# Particle_Feather_AdapterFeb2019v1.net
KiCad netlist of a schematic drawn in EAGLE
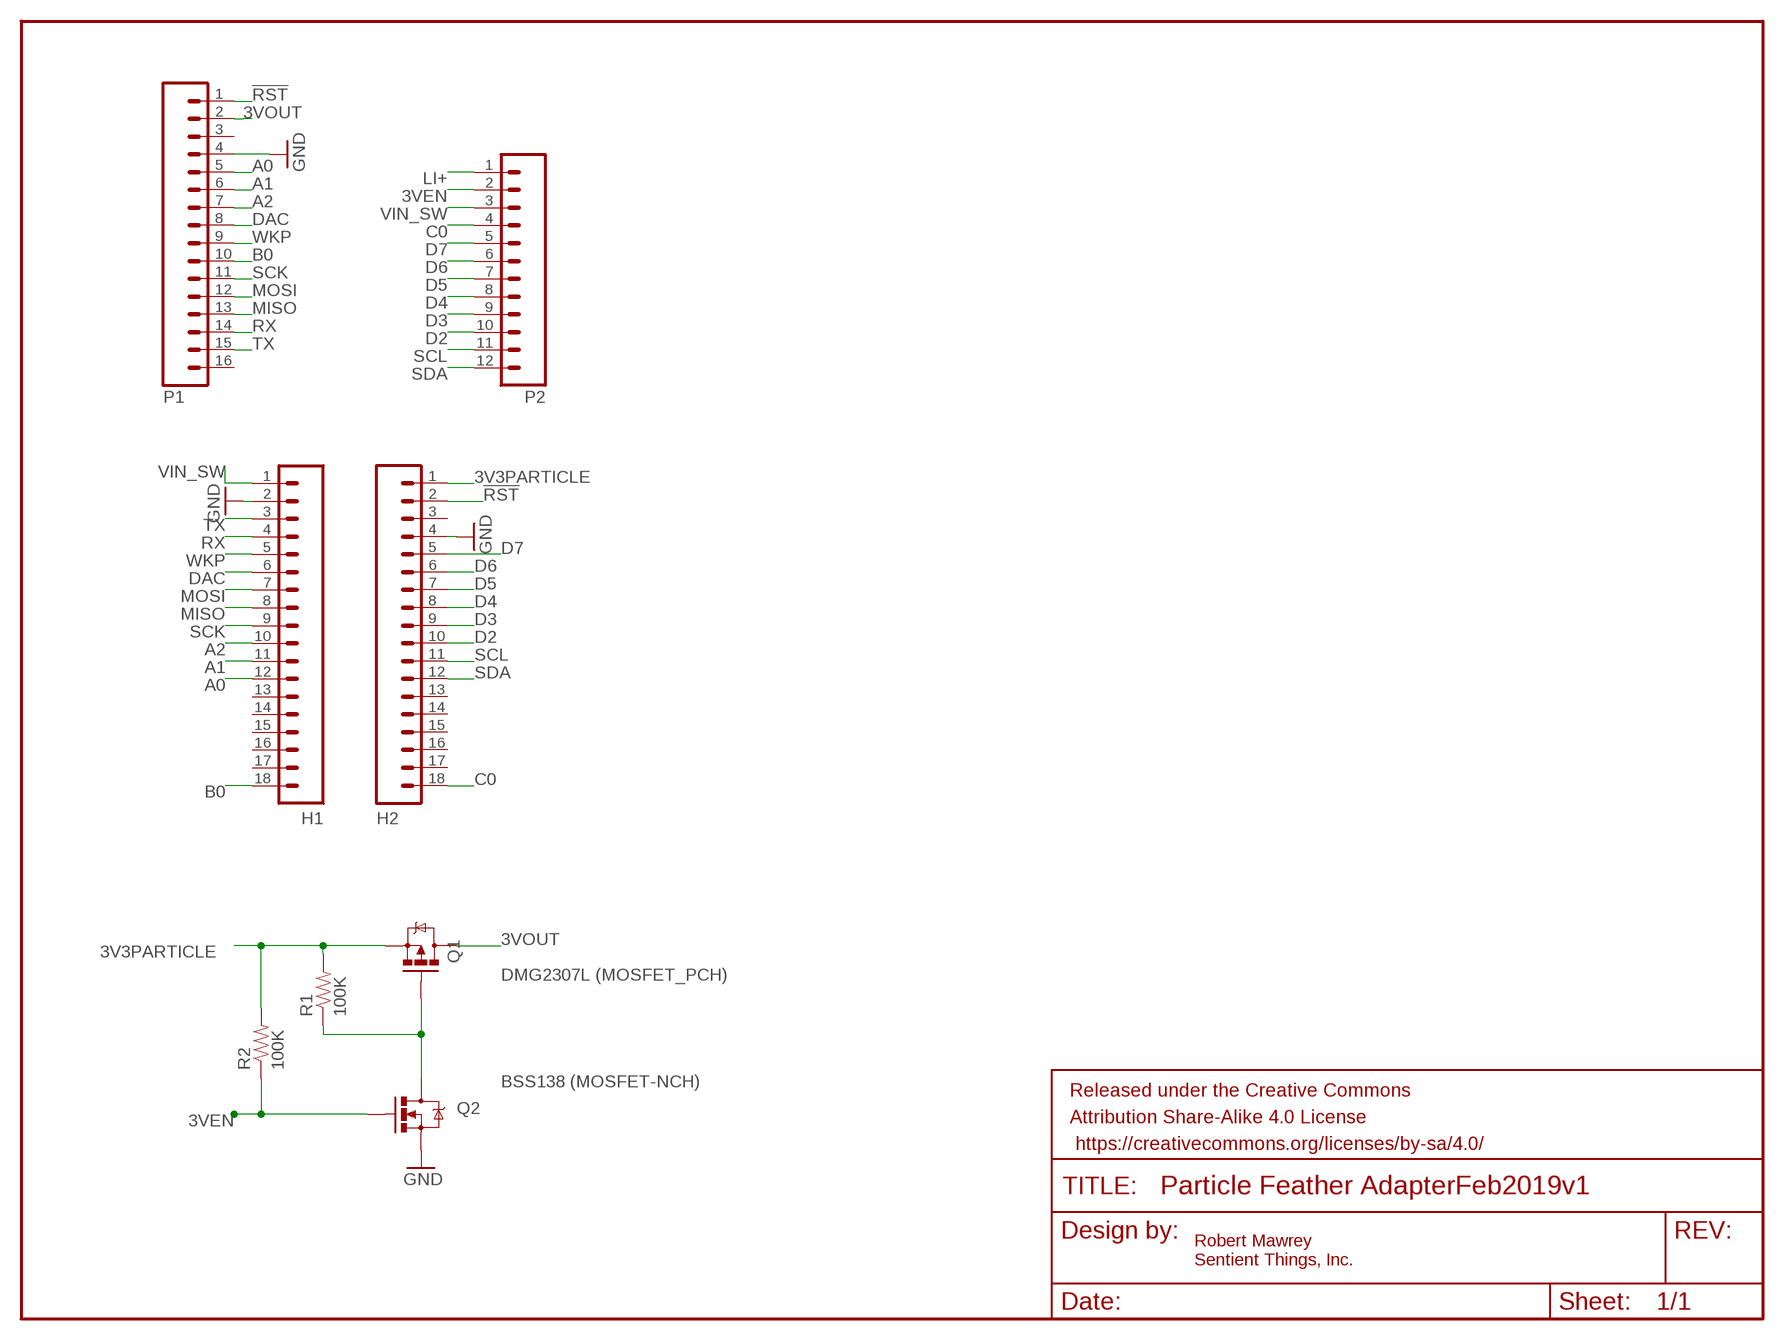
[diagram p0: schematic, sheet 1]

(export (version "E")
  (design (tool "Eeschema 10.0.6"))
  (components
    (comp (ref "FRAME1")
      (value "FRAME-LETTER")
      (footprint "eagle-import:CREATIVE_COMMONS")
      (fields (field (name "PARTNO") "DNP"))
      (libsource (lib "eagle-import") (part "FRAME-LETTER"))
    )
    (comp (ref "FRAME2")
      (value "FRAME-LETTER")
      (footprint "eagle-import:CREATIVE_COMMONS")
      (fields (field (name "PARTNO") "DNP"))
      (libsource (lib "eagle-import") (part "FRAME-LETTER"))
    )
    (comp (ref "H1")
      (value "M18-MILLMAX")
      (footprint "eagle-import:1X18-01SMD")
      (fields (field (name "PARTNO") "310-43-118-41-105000"))
      (libsource (lib "eagle-import") (part "M18-MILLMAX"))
    )
    (comp (ref "H2")
      (value "M18-MILLMAX")
      (footprint "eagle-import:1X18-01SMD")
      (fields (field (name "PARTNO") "310-43-118-41-105000"))
      (libsource (lib "eagle-import") (part "M18-MILLMAX"))
    )
    (comp (ref "P1")
      (value "M16-FEATHER")
      (footprint "eagle-import:1X16-01SMDRIGHT")
      (fields (field (name "PARTNO") "68016-116HLF"))
      (libsource (lib "eagle-import") (part "M16-FEATHER"))
    )
    (comp (ref "P2")
      (value "M12-FEATHER")
      (footprint "eagle-import:1X12-01SMDLEFT")
      (fields (field (name "PARTNO") "68016-212HLF"))
      (libsource (lib "eagle-import") (part "M12-FEATHER"))
    )
    (comp (ref "Q1")
      (value "MOSFET-PCHANNELSMD")
      (footprint "eagle-import:SOT23-3")
      (fields (field (name "PARTNO") "DMG2307L-7"))
      (libsource (lib "eagle-import") (part "MOSFET-PCHANNELSMD"))
    )
    (comp (ref "Q2")
      (value "MOSFET-NCHANNELSMD")
      (footprint "eagle-import:MAWREY_SOT23-3")
      (fields (field (name "PARTNO") "BSS138"))
      (libsource (lib "eagle-import") (part "MOSFET-NCHANNELSMD"))
    )
    (comp (ref "R1")
      (value "100K")
      (footprint "eagle-import:0603-RES")
      (fields (field (name "PARTNO") "RC0603JR-07100KL"))
      (libsource (lib "eagle-import") (part "RESISTOR0603-RES"))
    )
    (comp (ref "R2")
      (value "100K")
      (footprint "eagle-import:0603-RES")
      (fields (field (name "PARTNO") "RC0603JR-07100KL"))
      (libsource (lib "eagle-import") (part "RESISTOR0603-RES"))
    )
  )
  (nets
    (net (code "1") (name "/3V3PARTICLE") (class "Default")
      (node (ref "H2") (pin "1") (pinfunction "1_1") (pintype "passive"))
      (node (ref "Q1") (pin "2") (pinfunction "S_2") (pintype "passive"))
      (node (ref "R1") (pin "2") (pinfunction "2_2") (pintype "passive"))
      (node (ref "R2") (pin "2") (pinfunction "2_2") (pintype "passive"))
    )
    (net (code "2") (name "/3VEN") (class "Default")
      (node (ref "P2") (pin "2") (pinfunction "2_2") (pintype "passive"))
      (node (ref "Q2") (pin "1") (pinfunction "G_1") (pintype "passive"))
      (node (ref "R2") (pin "1") (pinfunction "1_1") (pintype "passive"))
    )
    (net (code "3") (name "/3VOUT") (class "Default")
      (node (ref "P1") (pin "2") (pinfunction "2_2") (pintype "passive"))
      (node (ref "Q1") (pin "3") (pinfunction "D_3") (pintype "passive"))
    )
    (net (code "4") (name "/A0") (class "Default")
      (node (ref "H1") (pin "12") (pinfunction "12_12") (pintype "passive"))
      (node (ref "P1") (pin "5") (pinfunction "5_5") (pintype "passive"))
    )
    (net (code "5") (name "/A1") (class "Default")
      (node (ref "H1") (pin "11") (pinfunction "11_11") (pintype "passive"))
      (node (ref "P1") (pin "6") (pinfunction "6_6") (pintype "passive"))
    )
    (net (code "6") (name "/A2") (class "Default")
      (node (ref "H1") (pin "10") (pinfunction "10_10") (pintype "passive"))
      (node (ref "P1") (pin "7") (pinfunction "7_7") (pintype "passive"))
    )
    (net (code "7") (name "/B0") (class "Default")
      (node (ref "H1") (pin "18") (pinfunction "18_18") (pintype "passive"))
      (node (ref "P1") (pin "10") (pinfunction "10_10") (pintype "passive"))
    )
    (net (code "8") (name "/C0") (class "Default")
      (node (ref "H2") (pin "18") (pinfunction "18_18") (pintype "passive"))
      (node (ref "P2") (pin "4") (pinfunction "4_4") (pintype "passive"))
    )
    (net (code "9") (name "/D2") (class "Default")
      (node (ref "H2") (pin "10") (pinfunction "10_10") (pintype "passive"))
      (node (ref "P2") (pin "10") (pinfunction "10_10") (pintype "passive"))
    )
    (net (code "10") (name "/D3") (class "Default")
      (node (ref "H2") (pin "9") (pinfunction "9_9") (pintype "passive"))
      (node (ref "P2") (pin "9") (pinfunction "9_9") (pintype "passive"))
    )
    (net (code "11") (name "/D4") (class "Default")
      (node (ref "H2") (pin "8") (pinfunction "8_8") (pintype "passive"))
      (node (ref "P2") (pin "8") (pinfunction "8_8") (pintype "passive"))
    )
    (net (code "12") (name "/D5") (class "Default")
      (node (ref "H2") (pin "7") (pinfunction "7_7") (pintype "passive"))
      (node (ref "P2") (pin "7") (pinfunction "7_7") (pintype "passive"))
    )
    (net (code "13") (name "/D6") (class "Default")
      (node (ref "H2") (pin "6") (pinfunction "6_6") (pintype "passive"))
      (node (ref "P2") (pin "6") (pinfunction "6_6") (pintype "passive"))
    )
    (net (code "14") (name "/D7") (class "Default")
      (node (ref "H2") (pin "5") (pinfunction "5_5") (pintype "passive"))
      (node (ref "P2") (pin "5") (pinfunction "5_5") (pintype "passive"))
    )
    (net (code "15") (name "/DAC") (class "Default")
      (node (ref "H1") (pin "6") (pinfunction "6_6") (pintype "passive"))
      (node (ref "P1") (pin "8") (pinfunction "8_8") (pintype "passive"))
    )
    (net (code "16") (name "/LI+") (class "Default")
      (node (ref "P2") (pin "1") (pinfunction "1_1") (pintype "passive"))
    )
    (net (code "17") (name "/MISO") (class "Default")
      (node (ref "H1") (pin "8") (pinfunction "8_8") (pintype "passive"))
      (node (ref "P1") (pin "13") (pinfunction "13_13") (pintype "passive"))
    )
    (net (code "18") (name "/MOSI") (class "Default")
      (node (ref "H1") (pin "7") (pinfunction "7_7") (pintype "passive"))
      (node (ref "P1") (pin "12") (pinfunction "12_12") (pintype "passive"))
    )
    (net (code "19") (name "/RX") (class "Default")
      (node (ref "H1") (pin "4") (pinfunction "4_4") (pintype "passive"))
      (node (ref "P1") (pin "14") (pinfunction "14_14") (pintype "passive"))
    )
    (net (code "20") (name "/SCK") (class "Default")
      (node (ref "H1") (pin "9") (pinfunction "9_9") (pintype "passive"))
      (node (ref "P1") (pin "11") (pinfunction "11_11") (pintype "passive"))
    )
    (net (code "21") (name "/SCL") (class "Default")
      (node (ref "H2") (pin "11") (pinfunction "11_11") (pintype "passive"))
      (node (ref "P2") (pin "11") (pinfunction "11_11") (pintype "passive"))
    )
    (net (code "22") (name "/SDA") (class "Default")
      (node (ref "H2") (pin "12") (pinfunction "12_12") (pintype "passive"))
      (node (ref "P2") (pin "12") (pinfunction "12_12") (pintype "passive"))
    )
    (net (code "23") (name "/TX") (class "Default")
      (node (ref "H1") (pin "3") (pinfunction "3_3") (pintype "passive"))
      (node (ref "P1") (pin "15") (pinfunction "15_15") (pintype "passive"))
    )
    (net (code "24") (name "/VIN_SW") (class "Default")
      (node (ref "H1") (pin "1") (pinfunction "1_1") (pintype "passive"))
      (node (ref "P2") (pin "3") (pinfunction "3_3") (pintype "passive"))
    )
    (net (code "25") (name "/WKP") (class "Default")
      (node (ref "H1") (pin "5") (pinfunction "5_5") (pintype "passive"))
      (node (ref "P1") (pin "9") (pinfunction "9_9") (pintype "passive"))
    )
    (net (code "26") (name "/~{RST}") (class "Default")
      (node (ref "H2") (pin "2") (pinfunction "2_2") (pintype "passive"))
      (node (ref "P1") (pin "1") (pinfunction "1_1") (pintype "passive"))
    )
    (net (code "27") (name "GND") (class "Default")
      (node (ref "H1") (pin "2") (pinfunction "2_2") (pintype "passive"))
      (node (ref "H2") (pin "4") (pinfunction "4_4") (pintype "passive"))
      (node (ref "P1") (pin "4") (pinfunction "4_4") (pintype "passive"))
      (node (ref "Q2") (pin "2") (pinfunction "S_2") (pintype "passive"))
    )
    (net (code "28") (name "Net-(Q1-G)") (class "Default")
      (node (ref "Q1") (pin "1") (pinfunction "G_1") (pintype "passive"))
      (node (ref "Q2") (pin "3") (pinfunction "D_3") (pintype "passive"))
      (node (ref "R1") (pin "1") (pinfunction "1_1") (pintype "passive"))
    )
    (net (code "29") (name "unconnected-(H1-Pad13)") (class "Default")
      (node (ref "H1") (pin "13") (pinfunction "13_13") (pintype "passive"))
    )
    (net (code "30") (name "unconnected-(H1-Pad14)") (class "Default")
      (node (ref "H1") (pin "14") (pinfunction "14_14") (pintype "passive"))
    )
    (net (code "31") (name "unconnected-(H1-Pad15)") (class "Default")
      (node (ref "H1") (pin "15") (pinfunction "15_15") (pintype "passive"))
    )
    (net (code "32") (name "unconnected-(H1-Pad16)") (class "Default")
      (node (ref "H1") (pin "16") (pinfunction "16_16") (pintype "passive"))
    )
    (net (code "33") (name "unconnected-(H1-Pad17)") (class "Default")
      (node (ref "H1") (pin "17") (pinfunction "17_17") (pintype "passive"))
    )
    (net (code "34") (name "unconnected-(H2-Pad3)") (class "Default")
      (node (ref "H2") (pin "3") (pinfunction "3_3") (pintype "passive"))
    )
    (net (code "35") (name "unconnected-(H2-Pad13)") (class "Default")
      (node (ref "H2") (pin "13") (pinfunction "13_13") (pintype "passive"))
    )
    (net (code "36") (name "unconnected-(H2-Pad14)") (class "Default")
      (node (ref "H2") (pin "14") (pinfunction "14_14") (pintype "passive"))
    )
    (net (code "37") (name "unconnected-(H2-Pad15)") (class "Default")
      (node (ref "H2") (pin "15") (pinfunction "15_15") (pintype "passive"))
    )
    (net (code "38") (name "unconnected-(H2-Pad16)") (class "Default")
      (node (ref "H2") (pin "16") (pinfunction "16_16") (pintype "passive"))
    )
    (net (code "39") (name "unconnected-(H2-Pad17)") (class "Default")
      (node (ref "H2") (pin "17") (pinfunction "17_17") (pintype "passive"))
    )
    (net (code "40") (name "unconnected-(P1-Pad3)") (class "Default")
      (node (ref "P1") (pin "3") (pinfunction "3_3") (pintype "passive"))
    )
    (net (code "41") (name "unconnected-(P1-Pad16)") (class "Default")
      (node (ref "P1") (pin "16") (pinfunction "16_16") (pintype "passive"))
    )
  )
)
